# uno.net
KiCad netlist of a schematic drawn in EAGLE
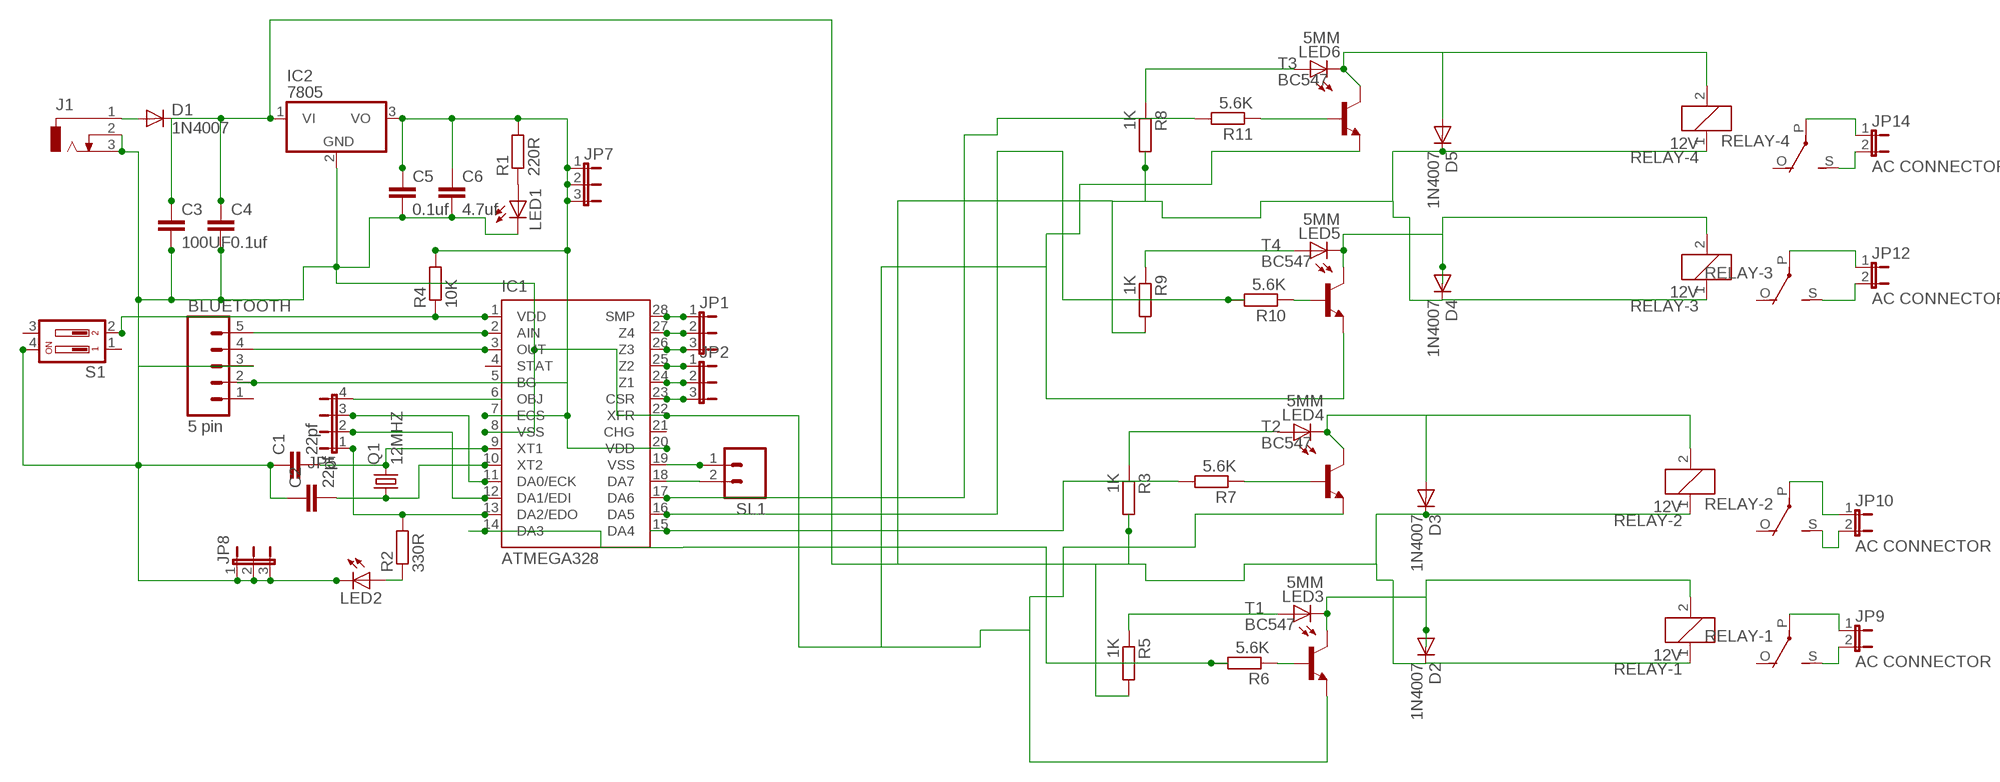
[diagram p0: schematic, sheet 1]

(export (version "E")
  (design (tool "Eeschema 10.0.6"))
  (components
    (comp (ref "BLUETOOTH")
      (value "5 pin")
      (footprint "eagle-import:05P")
      (libsource (lib "eagle-import") (part "M05"))
    )
    (comp (ref "C1")
      (value "22pf")
      (footprint "eagle-import:C2.5-2")
      (libsource (lib "eagle-import") (part "C2.5/2"))
    )
    (comp (ref "C2")
      (value "22pf")
      (footprint "eagle-import:C2.5-2")
      (libsource (lib "eagle-import") (part "C2.5/2"))
    )
    (comp (ref "C3")
      (value "100UF")
      (footprint "eagle-import:C2.5-2")
      (libsource (lib "eagle-import") (part "C2.5/2"))
    )
    (comp (ref "C4")
      (value "0.1uf")
      (footprint "eagle-import:C2.5-2")
      (libsource (lib "eagle-import") (part "C2.5/2"))
    )
    (comp (ref "C5")
      (value "0.1uf")
      (footprint "eagle-import:C2.5-2")
      (libsource (lib "eagle-import") (part "C2.5/2"))
    )
    (comp (ref "C6")
      (value "4.7uf")
      (footprint "eagle-import:C2.5-2")
      (libsource (lib "eagle-import") (part "C2.5/2"))
    )
    (comp (ref "D1")
      (value "1N4007")
      (footprint "eagle-import:DO41-10")
      (libsource (lib "eagle-import") (part "1N4004"))
    )
    (comp (ref "D2")
      (value "1N4007")
      (footprint "eagle-import:DO41-10")
      (libsource (lib "eagle-import") (part "1N4004"))
    )
    (comp (ref "D3")
      (value "1N4007")
      (footprint "eagle-import:DO41-10")
      (libsource (lib "eagle-import") (part "1N4004"))
    )
    (comp (ref "D4")
      (value "1N4007")
      (footprint "eagle-import:DO41-10")
      (libsource (lib "eagle-import") (part "1N4004"))
    )
    (comp (ref "D5")
      (value "1N4007")
      (footprint "eagle-import:DO41-10")
      (libsource (lib "eagle-import") (part "1N4004"))
    )
    (comp (ref "IC1")
      (value "ATMEGA328")
      (footprint "eagle-import:DIL28-3")
      (libsource (lib "eagle-import") (part "QT9701BD"))
    )
    (comp (ref "IC2")
      (value "7805")
      (footprint "eagle-import:TO220V")
      (libsource (lib "eagle-import") (part "78TV6"))
    )
    (comp (ref "J1")
      (value "DCJ0303")
      (footprint "eagle-import:DCJ0303")
      (libsource (lib "eagle-import") (part "DCJ0303"))
    )
    (comp (ref "JP1")
      (value "JP2E")
      (footprint "eagle-import:JP2")
      (libsource (lib "eagle-import") (part "JP2E"))
    )
    (comp (ref "JP2")
      (value "JP2E")
      (footprint "eagle-import:JP2")
      (libsource (lib "eagle-import") (part "JP2E"))
    )
    (comp (ref "JP5")
      (value "JP4E")
      (footprint "eagle-import:JP4")
      (libsource (lib "eagle-import") (part "JP4E"))
    )
    (comp (ref "JP7")
      (value "JP2E")
      (footprint "eagle-import:JP2")
      (libsource (lib "eagle-import") (part "JP2E"))
    )
    (comp (ref "JP8")
      (value "JP2E")
      (footprint "eagle-import:JP2")
      (libsource (lib "eagle-import") (part "JP2E"))
    )
    (comp (ref "JP9")
      (value "AC CONNECTOR")
      (footprint "eagle-import:JP1")
      (libsource (lib "eagle-import") (part "JP1E"))
    )
    (comp (ref "JP10")
      (value "AC CONNECTOR")
      (footprint "eagle-import:JP1")
      (libsource (lib "eagle-import") (part "JP1E"))
    )
    (comp (ref "JP12")
      (value "AC CONNECTOR")
      (footprint "eagle-import:JP1")
      (libsource (lib "eagle-import") (part "JP1E"))
    )
    (comp (ref "JP14")
      (value "AC CONNECTOR")
      (footprint "eagle-import:JP1")
      (libsource (lib "eagle-import") (part "JP1E"))
    )
    (comp (ref "LED1")
      (value "LED3MM")
      (footprint "eagle-import:LED3MM")
      (libsource (lib "eagle-import") (part "LED3MM"))
    )
    (comp (ref "LED2")
      (value "LED3MM")
      (footprint "eagle-import:LED3MM")
      (libsource (lib "eagle-import") (part "LED3MM"))
    )
    (comp (ref "LED3")
      (value "5MM")
      (footprint "eagle-import:LED5MM")
      (libsource (lib "eagle-import") (part "LED5MM"))
    )
    (comp (ref "LED4")
      (value "5MM")
      (footprint "eagle-import:LED5MM")
      (libsource (lib "eagle-import") (part "LED5MM"))
    )
    (comp (ref "LED5")
      (value "5MM")
      (footprint "eagle-import:LED5MM")
      (libsource (lib "eagle-import") (part "LED5MM"))
    )
    (comp (ref "LED6")
      (value "5MM")
      (footprint "eagle-import:LED5MM")
      (libsource (lib "eagle-import") (part "LED5MM"))
    )
    (comp (ref "Q1")
      (value "12MHZ")
      (footprint "eagle-import:HC49_S")
      (libsource (lib "eagle-import") (part "CRYSTALHC49S"))
    )
    (comp (ref "R1")
      (value "220R")
      (footprint "eagle-import:0207_10")
      (libsource (lib "eagle-import") (part "R-EU_0207/10"))
    )
    (comp (ref "R2")
      (value "330R")
      (footprint "eagle-import:0207_10")
      (libsource (lib "eagle-import") (part "R-EU_0207/10"))
    )
    (comp (ref "R3")
      (value "1K")
      (footprint "eagle-import:0204_7")
      (libsource (lib "eagle-import") (part "R-EU_0204/7"))
    )
    (comp (ref "R4")
      (value "10K")
      (footprint "eagle-import:0207_10")
      (libsource (lib "eagle-import") (part "R-EU_0207/10"))
    )
    (comp (ref "R5")
      (value "1K")
      (footprint "eagle-import:0204_7")
      (libsource (lib "eagle-import") (part "R-EU_0204/7"))
    )
    (comp (ref "R6")
      (value "5.6K")
      (footprint "eagle-import:0204_7")
      (libsource (lib "eagle-import") (part "R-EU_0204/7"))
    )
    (comp (ref "R7")
      (value "5.6K")
      (footprint "eagle-import:0204_7")
      (libsource (lib "eagle-import") (part "R-EU_0204/7"))
    )
    (comp (ref "R8")
      (value "1K")
      (footprint "eagle-import:0204_7")
      (libsource (lib "eagle-import") (part "R-EU_0204/7"))
    )
    (comp (ref "R9")
      (value "1K")
      (footprint "eagle-import:0204_7")
      (libsource (lib "eagle-import") (part "R-EU_0204/7"))
    )
    (comp (ref "R10")
      (value "5.6K")
      (footprint "eagle-import:0204_7")
      (libsource (lib "eagle-import") (part "R-EU_0204/7"))
    )
    (comp (ref "R11")
      (value "5.6K")
      (footprint "eagle-import:0204_7")
      (libsource (lib "eagle-import") (part "R-EU_0204/7"))
    )
    (comp (ref "RELAY-1")
      (value "12V")
      (footprint "eagle-import:G5LE")
      (libsource (lib "eagle-import") (part "G5L"))
    )
    (comp (ref "RELAY-2")
      (value "12V")
      (footprint "eagle-import:G5LE")
      (libsource (lib "eagle-import") (part "G5L"))
    )
    (comp (ref "RELAY-3")
      (value "12V")
      (footprint "eagle-import:G5LE")
      (libsource (lib "eagle-import") (part "G5L"))
    )
    (comp (ref "RELAY-4")
      (value "12V")
      (footprint "eagle-import:G5LE")
      (libsource (lib "eagle-import") (part "G5L"))
    )
    (comp (ref "S1")
      (value "DP02")
      (footprint "eagle-import:DP-02")
      (fields (field (name "MPN") "MCDP02"))
      (libsource (lib "eagle-import") (part "DP02"))
    )
    (comp (ref "SL1")
      (value "M02")
      (footprint "eagle-import:02P")
      (libsource (lib "eagle-import") (part "M02"))
    )
    (comp (ref "T1")
      (value "BC547")
      (footprint "eagle-import:TO92")
      (libsource (lib "eagle-import") (part "BC547"))
    )
    (comp (ref "T2")
      (value "BC547")
      (footprint "eagle-import:TO92")
      (libsource (lib "eagle-import") (part "BC547"))
    )
    (comp (ref "T3")
      (value "BC547")
      (footprint "eagle-import:TO92")
      (libsource (lib "eagle-import") (part "BC547"))
    )
    (comp (ref "T4")
      (value "BC547")
      (footprint "eagle-import:TO92")
      (libsource (lib "eagle-import") (part "BC547"))
    )
  )
  (nets
    (net (code "1") (name "Net-(D1-PadA)") (class "Default")
      (node (ref "D1") (pin "A") (pinfunction "A_A") (pintype "passive"))
      (node (ref "J1") (pin "1") (pinfunction "1_1") (pintype "passive"))
    )
    (net (code "2") (name "Net-(IC1-AIN)") (class "Default")
      (node (ref "BLUETOOTH") (pin "5") (pinfunction "5_5") (pintype "passive"))
      (node (ref "IC1") (pin "2") (pinfunction "AIN_2") (pintype "input"))
    )
    (net (code "3") (name "Net-(IC1-CSR)") (class "Default")
      (node (ref "IC1") (pin "23") (pinfunction "CSR_23") (pintype "output"))
      (node (ref "JP2") (pin "3") (pinfunction "3_3") (pintype "passive"))
    )
    (net (code "4") (name "Net-(IC1-DA0{slash}ECK)") (class "Default")
      (node (ref "IC1") (pin "11") (pinfunction "DA0/ECK_11") (pintype "output"))
      (node (ref "JP5") (pin "3") (pinfunction "3_3") (pintype "passive"))
    )
    (net (code "5") (name "Net-(IC1-DA1{slash}EDI)") (class "Default")
      (node (ref "IC1") (pin "12") (pinfunction "DA1/EDI_12") (pintype "output"))
      (node (ref "JP5") (pin "2") (pinfunction "2_2") (pintype "passive"))
    )
    (net (code "6") (name "Net-(IC1-DA2{slash}EDO)") (class "Default")
      (node (ref "IC1") (pin "13") (pinfunction "DA2/EDO_13") (pintype "output"))
      (node (ref "JP5") (pin "1") (pinfunction "1_1") (pintype "passive"))
      (node (ref "R2") (pin "2") (pinfunction "2_2") (pintype "passive"))
    )
    (net (code "7") (name "Net-(IC1-DA3)") (class "Default")
      (node (ref "IC1") (pin "14") (pinfunction "DA3_14") (pintype "output"))
      (node (ref "R6") (pin "2") (pinfunction "2_2") (pintype "passive"))
    )
    (net (code "8") (name "Net-(IC1-DA4)") (class "Default")
      (node (ref "IC1") (pin "15") (pinfunction "DA4_15") (pintype "output"))
      (node (ref "R7") (pin "2") (pinfunction "2_2") (pintype "passive"))
    )
    (net (code "9") (name "Net-(IC1-DA5)") (class "Default")
      (node (ref "IC1") (pin "16") (pinfunction "DA5_16") (pintype "output"))
      (node (ref "R10") (pin "2") (pinfunction "2_2") (pintype "passive"))
    )
    (net (code "10") (name "Net-(IC1-DA6)") (class "Default")
      (node (ref "IC1") (pin "17") (pinfunction "DA6_17") (pintype "output"))
      (node (ref "R11") (pin "2") (pinfunction "2_2") (pintype "passive"))
    )
    (net (code "11") (name "Net-(IC1-DA7)") (class "Default")
      (node (ref "IC1") (pin "18") (pinfunction "DA7_18") (pintype "output"))
      (node (ref "SL1") (pin "2") (pinfunction "2_2") (pintype "passive"))
    )
    (net (code "12") (name "Net-(IC1-ECS)") (class "Default")
      (node (ref "BLUETOOTH") (pin "2") (pinfunction "2_2") (pintype "passive"))
      (node (ref "C5") (pin "1") (pinfunction "1_1") (pintype "passive"))
      (node (ref "C6") (pin "1") (pinfunction "1_1") (pintype "passive"))
      (node (ref "IC1") (pin "20") (pinfunction "VDD_20") (pintype "input"))
      (node (ref "IC1") (pin "7") (pinfunction "ECS_7") (pintype "output"))
      (node (ref "IC2") (pin "3") (pinfunction "VO_3") (pintype "passive"))
      (node (ref "JP7") (pin "1") (pinfunction "1_1") (pintype "passive"))
      (node (ref "JP7") (pin "2") (pinfunction "2_2") (pintype "passive"))
      (node (ref "JP7") (pin "3") (pinfunction "3_3") (pintype "passive"))
      (node (ref "R1") (pin "2") (pinfunction "2_2") (pintype "passive"))
      (node (ref "R4") (pin "2") (pinfunction "2_2") (pintype "passive"))
    )
    (net (code "13") (name "Net-(IC1-OUT)") (class "Default")
      (node (ref "BLUETOOTH") (pin "4") (pinfunction "4_4") (pintype "passive"))
      (node (ref "IC1") (pin "3") (pinfunction "OUT_3") (pintype "output"))
    )
    (net (code "14") (name "Net-(IC1-SMP)") (class "Default")
      (node (ref "IC1") (pin "28") (pinfunction "SMP_28") (pintype "output"))
      (node (ref "JP1") (pin "1") (pinfunction "1_1") (pintype "passive"))
    )
    (net (code "15") (name "Net-(IC1-VDD-Pad1)") (class "Default")
      (node (ref "IC1") (pin "1") (pinfunction "VDD_1") (pintype "input"))
      (node (ref "R4") (pin "1") (pinfunction "1_1") (pintype "passive"))
      (node (ref "S1") (pin "2") (pinfunction "2_2") (pintype "passive"))
    )
    (net (code "16") (name "Net-(IC1-VSS-Pad19)") (class "Default")
      (node (ref "IC1") (pin "19") (pinfunction "VSS_19") (pintype "input"))
      (node (ref "SL1") (pin "1") (pinfunction "1_1") (pintype "passive"))
    )
    (net (code "17") (name "Net-(IC1-XFR)") (class "Default")
      (node (ref "BLUETOOTH") (pin "3") (pinfunction "3_3") (pintype "passive"))
      (node (ref "C1") (pin "1") (pinfunction "1_1") (pintype "passive"))
      (node (ref "C2") (pin "1") (pinfunction "1_1") (pintype "passive"))
      (node (ref "C3") (pin "2") (pinfunction "2_2") (pintype "passive"))
      (node (ref "C4") (pin "2") (pinfunction "2_2") (pintype "passive"))
      (node (ref "C5") (pin "2") (pinfunction "2_2") (pintype "passive"))
      (node (ref "C6") (pin "2") (pinfunction "2_2") (pintype "passive"))
      (node (ref "IC1") (pin "22") (pinfunction "XFR_22") (pintype "output"))
      (node (ref "IC1") (pin "8") (pinfunction "VSS_8") (pintype "input"))
      (node (ref "IC2") (pin "2") (pinfunction "GND_2") (pintype "passive"))
      (node (ref "J1") (pin "2") (pinfunction "2_2") (pintype "passive"))
      (node (ref "J1") (pin "3") (pinfunction "3_3") (pintype "passive"))
      (node (ref "JP8") (pin "1") (pinfunction "1_1") (pintype "passive"))
      (node (ref "JP8") (pin "2") (pinfunction "2_2") (pintype "passive"))
      (node (ref "JP8") (pin "3") (pinfunction "3_3") (pintype "passive"))
      (node (ref "LED1") (pin "K") (pinfunction "C_K") (pintype "passive"))
      (node (ref "LED2") (pin "K") (pinfunction "C_K") (pintype "passive"))
      (node (ref "S1") (pin "4") (pinfunction "4_4") (pintype "passive"))
      (node (ref "T1") (pin "1") (pinfunction "E_1") (pintype "passive"))
      (node (ref "T2") (pin "1") (pinfunction "E_1") (pintype "passive"))
      (node (ref "T3") (pin "1") (pinfunction "E_1") (pintype "passive"))
      (node (ref "T4") (pin "1") (pinfunction "E_1") (pintype "passive"))
    )
    (net (code "18") (name "Net-(IC1-XT1)") (class "Default")
      (node (ref "C1") (pin "2") (pinfunction "2_2") (pintype "passive"))
      (node (ref "IC1") (pin "9") (pinfunction "XT1_9") (pintype "input"))
      (node (ref "Q1") (pin "2") (pinfunction "2_2") (pintype "passive"))
    )
    (net (code "19") (name "Net-(IC1-XT2)") (class "Default")
      (node (ref "C2") (pin "2") (pinfunction "2_2") (pintype "passive"))
      (node (ref "IC1") (pin "10") (pinfunction "XT2_10") (pintype "output"))
      (node (ref "Q1") (pin "1") (pinfunction "1_1") (pintype "passive"))
    )
    (net (code "20") (name "Net-(IC1-Z1)") (class "Default")
      (node (ref "IC1") (pin "24") (pinfunction "Z1_24") (pintype "output"))
      (node (ref "JP2") (pin "2") (pinfunction "2_2") (pintype "passive"))
    )
    (net (code "21") (name "Net-(IC1-Z2)") (class "Default")
      (node (ref "IC1") (pin "25") (pinfunction "Z2_25") (pintype "output"))
      (node (ref "JP2") (pin "1") (pinfunction "1_1") (pintype "passive"))
    )
    (net (code "22") (name "Net-(IC1-Z3)") (class "Default")
      (node (ref "IC1") (pin "26") (pinfunction "Z3_26") (pintype "output"))
      (node (ref "JP1") (pin "3") (pinfunction "3_3") (pintype "passive"))
    )
    (net (code "23") (name "Net-(IC1-Z4)") (class "Default")
      (node (ref "IC1") (pin "27") (pinfunction "Z4_27") (pintype "output"))
      (node (ref "JP1") (pin "2") (pinfunction "2_2") (pintype "passive"))
    )
    (net (code "24") (name "Net-(IC2-VI)") (class "Default")
      (node (ref "C3") (pin "1") (pinfunction "1_1") (pintype "passive"))
      (node (ref "C4") (pin "1") (pinfunction "1_1") (pintype "passive"))
      (node (ref "D1") (pin "C") (pinfunction "C_C") (pintype "passive"))
      (node (ref "D2") (pin "C") (pinfunction "C_C") (pintype "passive"))
      (node (ref "D3") (pin "C") (pinfunction "C_C") (pintype "passive"))
      (node (ref "D4") (pin "C") (pinfunction "C_C") (pintype "passive"))
      (node (ref "D5") (pin "C") (pinfunction "C_C") (pintype "passive"))
      (node (ref "IC2") (pin "1") (pinfunction "VI_1") (pintype "input"))
      (node (ref "R3") (pin "2") (pinfunction "2_2") (pintype "passive"))
      (node (ref "R5") (pin "2") (pinfunction "2_2") (pintype "passive"))
      (node (ref "R8") (pin "2") (pinfunction "2_2") (pintype "passive"))
      (node (ref "R9") (pin "2") (pinfunction "2_2") (pintype "passive"))
      (node (ref "RELAY-1") (pin "1") (pinfunction "1_1") (pintype "passive"))
      (node (ref "RELAY-2") (pin "1") (pinfunction "1_1") (pintype "passive"))
      (node (ref "RELAY-3") (pin "1") (pinfunction "1_1") (pintype "passive"))
      (node (ref "RELAY-4") (pin "1") (pinfunction "1_1") (pintype "passive"))
    )
    (net (code "25") (name "Net-(JP9-Pad1)") (class "Default")
      (node (ref "JP9") (pin "1") (pinfunction "1_1") (pintype "passive"))
      (node (ref "RELAY-1") (pin "P") (pinfunction "P_P") (pintype "passive"))
    )
    (net (code "26") (name "Net-(JP9-Pad2)") (class "Default")
      (node (ref "JP9") (pin "2") (pinfunction "2_2") (pintype "passive"))
      (node (ref "RELAY-1") (pin "S") (pinfunction "S_S") (pintype "passive"))
    )
    (net (code "27") (name "Net-(JP10-Pad1)") (class "Default")
      (node (ref "JP10") (pin "1") (pinfunction "1_1") (pintype "passive"))
      (node (ref "RELAY-2") (pin "P") (pinfunction "P_P") (pintype "passive"))
    )
    (net (code "28") (name "Net-(JP10-Pad2)") (class "Default")
      (node (ref "JP10") (pin "2") (pinfunction "2_2") (pintype "passive"))
      (node (ref "RELAY-2") (pin "S") (pinfunction "S_S") (pintype "passive"))
    )
    (net (code "29") (name "Net-(JP12-Pad1)") (class "Default")
      (node (ref "JP12") (pin "1") (pinfunction "1_1") (pintype "passive"))
      (node (ref "RELAY-3") (pin "P") (pinfunction "P_P") (pintype "passive"))
    )
    (net (code "30") (name "Net-(JP12-Pad2)") (class "Default")
      (node (ref "JP12") (pin "2") (pinfunction "2_2") (pintype "passive"))
      (node (ref "RELAY-3") (pin "S") (pinfunction "S_S") (pintype "passive"))
    )
    (net (code "31") (name "Net-(JP14-Pad1)") (class "Default")
      (node (ref "JP14") (pin "1") (pinfunction "1_1") (pintype "passive"))
      (node (ref "RELAY-4") (pin "P") (pinfunction "P_P") (pintype "passive"))
    )
    (net (code "32") (name "Net-(JP14-Pad2)") (class "Default")
      (node (ref "JP14") (pin "2") (pinfunction "2_2") (pintype "passive"))
      (node (ref "RELAY-4") (pin "S") (pinfunction "S_S") (pintype "passive"))
    )
    (net (code "33") (name "Net-(LED1-PadA)") (class "Default")
      (node (ref "LED1") (pin "A") (pinfunction "A_A") (pintype "passive"))
      (node (ref "R1") (pin "1") (pinfunction "1_1") (pintype "passive"))
    )
    (net (code "34") (name "Net-(LED2-PadA)") (class "Default")
      (node (ref "LED2") (pin "A") (pinfunction "A_A") (pintype "passive"))
      (node (ref "R2") (pin "1") (pinfunction "1_1") (pintype "passive"))
    )
    (net (code "35") (name "Net-(LED3-C)") (class "Default")
      (node (ref "D2") (pin "A") (pinfunction "A_A") (pintype "passive"))
      (node (ref "LED3") (pin "K") (pinfunction "C_K") (pintype "passive"))
      (node (ref "RELAY-1") (pin "2") (pinfunction "2_2") (pintype "passive"))
      (node (ref "T1") (pin "3") (pinfunction "C_3") (pintype "passive"))
    )
    (net (code "36") (name "Net-(LED3-PadA)") (class "Default")
      (node (ref "LED3") (pin "A") (pinfunction "A_A") (pintype "passive"))
      (node (ref "R5") (pin "1") (pinfunction "1_1") (pintype "passive"))
    )
    (net (code "37") (name "Net-(LED4-C)") (class "Default")
      (node (ref "D3") (pin "A") (pinfunction "A_A") (pintype "passive"))
      (node (ref "LED4") (pin "K") (pinfunction "C_K") (pintype "passive"))
      (node (ref "RELAY-2") (pin "2") (pinfunction "2_2") (pintype "passive"))
      (node (ref "T2") (pin "3") (pinfunction "C_3") (pintype "passive"))
    )
    (net (code "38") (name "Net-(LED4-PadA)") (class "Default")
      (node (ref "LED4") (pin "A") (pinfunction "A_A") (pintype "passive"))
      (node (ref "R3") (pin "1") (pinfunction "1_1") (pintype "passive"))
    )
    (net (code "39") (name "Net-(LED5-C)") (class "Default")
      (node (ref "D4") (pin "A") (pinfunction "A_A") (pintype "passive"))
      (node (ref "LED5") (pin "K") (pinfunction "C_K") (pintype "passive"))
      (node (ref "RELAY-3") (pin "2") (pinfunction "2_2") (pintype "passive"))
      (node (ref "T4") (pin "3") (pinfunction "C_3") (pintype "passive"))
    )
    (net (code "40") (name "Net-(LED5-PadA)") (class "Default")
      (node (ref "LED5") (pin "A") (pinfunction "A_A") (pintype "passive"))
      (node (ref "R9") (pin "1") (pinfunction "1_1") (pintype "passive"))
    )
    (net (code "41") (name "Net-(LED6-C)") (class "Default")
      (node (ref "D5") (pin "A") (pinfunction "A_A") (pintype "passive"))
      (node (ref "LED6") (pin "K") (pinfunction "C_K") (pintype "passive"))
      (node (ref "RELAY-4") (pin "2") (pinfunction "2_2") (pintype "passive"))
      (node (ref "T3") (pin "3") (pinfunction "C_3") (pintype "passive"))
    )
    (net (code "42") (name "Net-(LED6-PadA)") (class "Default")
      (node (ref "LED6") (pin "A") (pinfunction "A_A") (pintype "passive"))
      (node (ref "R8") (pin "1") (pinfunction "1_1") (pintype "passive"))
    )
    (net (code "43") (name "Net-(T1-B)") (class "Default")
      (node (ref "R6") (pin "1") (pinfunction "1_1") (pintype "passive"))
      (node (ref "T1") (pin "2") (pinfunction "B_2") (pintype "passive"))
    )
    (net (code "44") (name "Net-(T2-B)") (class "Default")
      (node (ref "R7") (pin "1") (pinfunction "1_1") (pintype "passive"))
      (node (ref "T2") (pin "2") (pinfunction "B_2") (pintype "passive"))
    )
    (net (code "45") (name "Net-(T3-B)") (class "Default")
      (node (ref "R11") (pin "1") (pinfunction "1_1") (pintype "passive"))
      (node (ref "T3") (pin "2") (pinfunction "B_2") (pintype "passive"))
    )
    (net (code "46") (name "Net-(T4-B)") (class "Default")
      (node (ref "R10") (pin "1") (pinfunction "1_1") (pintype "passive"))
      (node (ref "T4") (pin "2") (pinfunction "B_2") (pintype "passive"))
    )
    (net (code "47") (name "unconnected-(BLUETOOTH-Pad1)") (class "Default")
      (node (ref "BLUETOOTH") (pin "1") (pinfunction "1_1") (pintype "passive"))
    )
    (net (code "48") (name "unconnected-(IC1-BG-Pad5)") (class "Default")
      (node (ref "IC1") (pin "5") (pinfunction "BG_5") (pintype "input"))
    )
    (net (code "49") (name "unconnected-(IC1-CHG-Pad21)") (class "Default")
      (node (ref "IC1") (pin "21") (pinfunction "CHG_21") (pintype "output"))
    )
    (net (code "50") (name "unconnected-(IC1-OBJ-Pad6)") (class "Default")
      (node (ref "IC1") (pin "6") (pinfunction "OBJ_6") (pintype "input"))
    )
    (net (code "51") (name "unconnected-(IC1-STAT-Pad4)") (class "Default")
      (node (ref "IC1") (pin "4") (pinfunction "STAT_4") (pintype "output"))
    )
    (net (code "52") (name "unconnected-(JP5-Pad4)") (class "Default")
      (node (ref "JP5") (pin "4") (pinfunction "4_4") (pintype "passive"))
    )
    (net (code "53") (name "unconnected-(RELAY-1-PadO)") (class "Default")
      (node (ref "RELAY-1") (pin "O") (pinfunction "O_O") (pintype "passive"))
    )
    (net (code "54") (name "unconnected-(RELAY-2-PadO)") (class "Default")
      (node (ref "RELAY-2") (pin "O") (pinfunction "O_O") (pintype "passive"))
    )
    (net (code "55") (name "unconnected-(RELAY-3-PadO)") (class "Default")
      (node (ref "RELAY-3") (pin "O") (pinfunction "O_O") (pintype "passive"))
    )
    (net (code "56") (name "unconnected-(RELAY-4-PadO)") (class "Default")
      (node (ref "RELAY-4") (pin "O") (pinfunction "O_O") (pintype "passive"))
    )
    (net (code "57") (name "unconnected-(S1-Pad1)") (class "Default")
      (node (ref "S1") (pin "1") (pinfunction "1_1") (pintype "passive"))
    )
    (net (code "58") (name "unconnected-(S1-Pad3)") (class "Default")
      (node (ref "S1") (pin "3") (pinfunction "3_3") (pintype "passive"))
    )
  )
)
